# MAD76.net
KiCad netlist of a schematic drawn in EAGLE
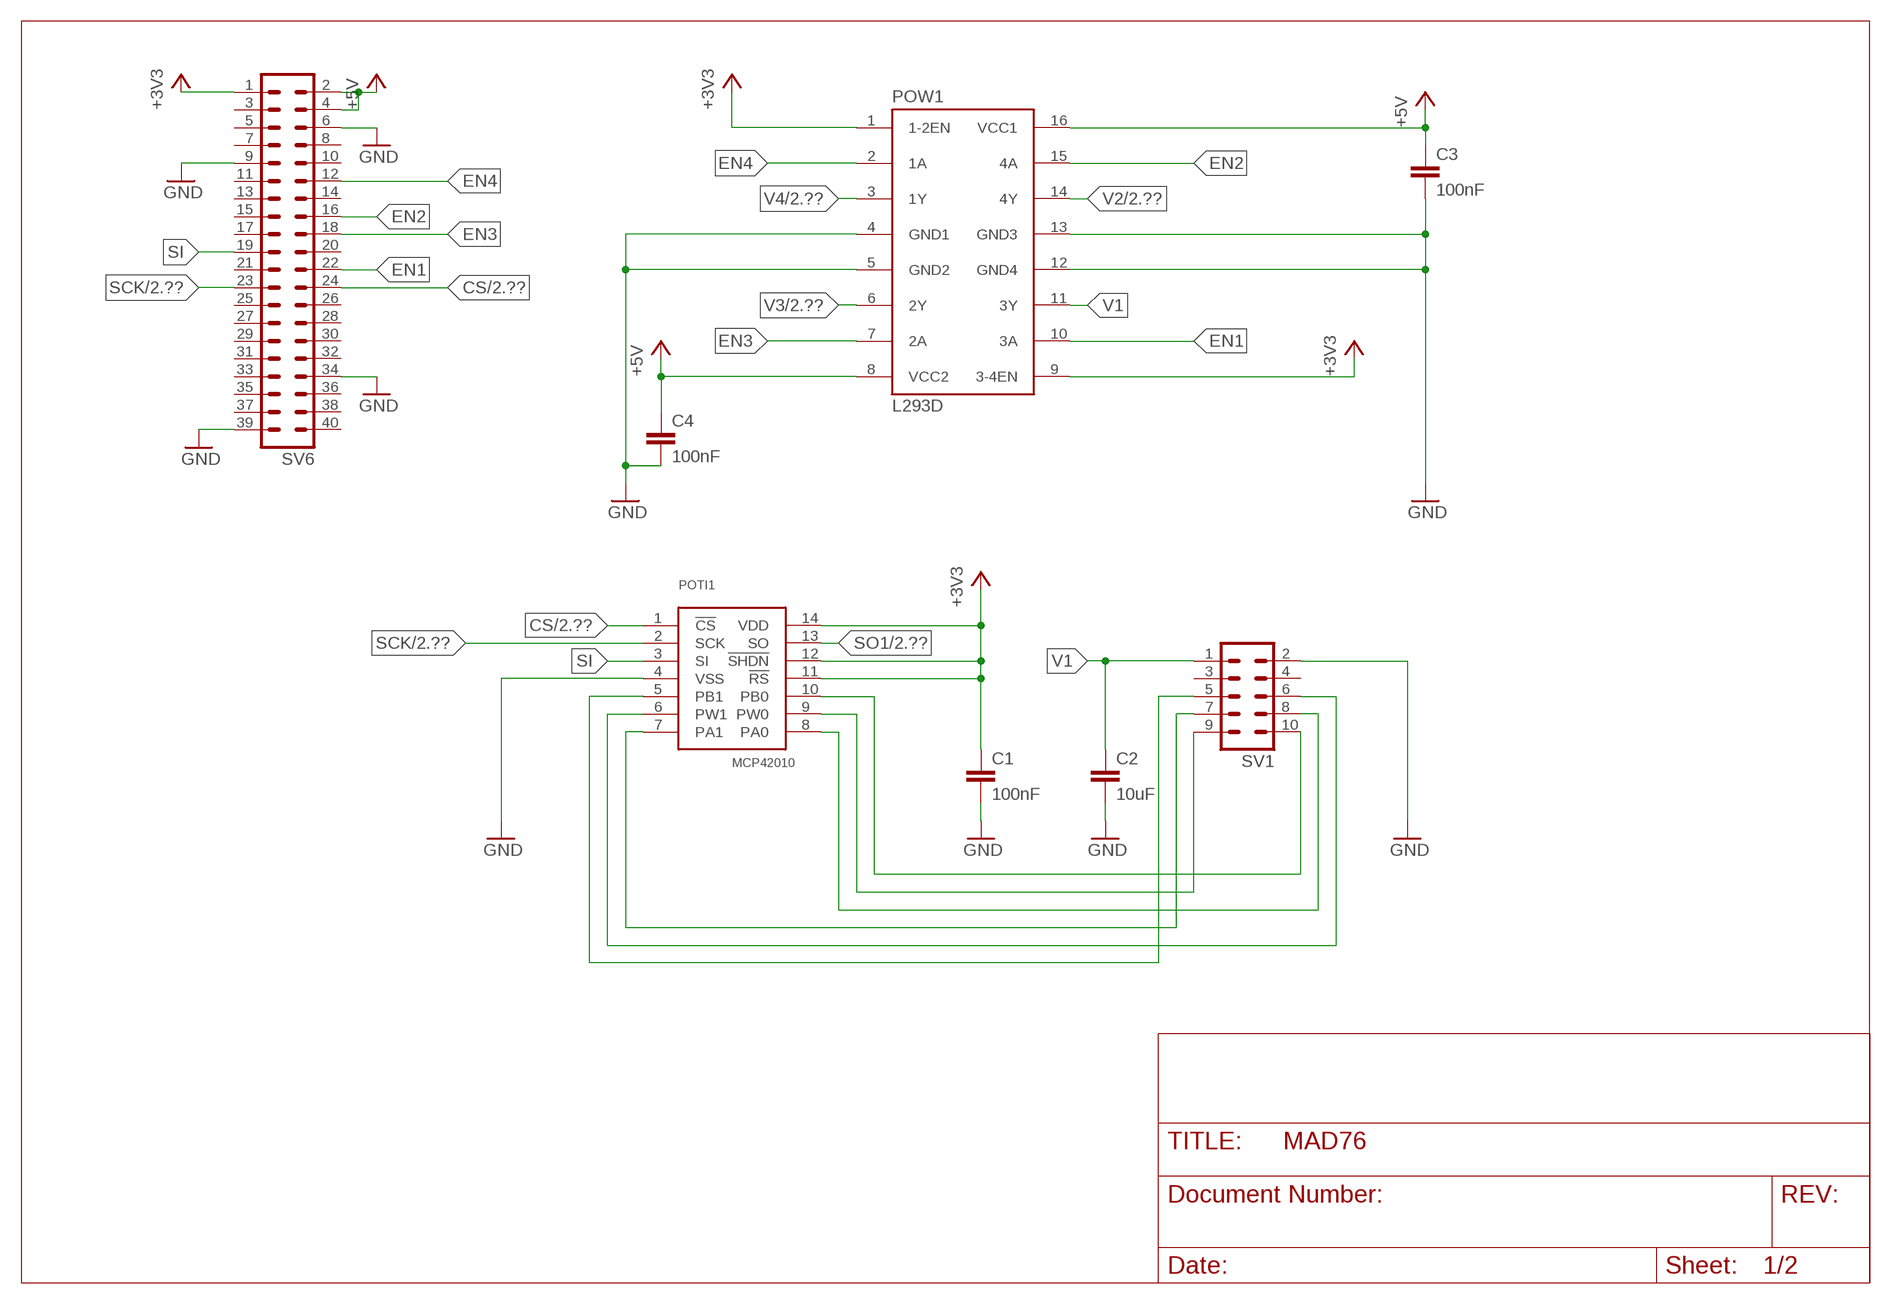
[diagram p0: schematic, sheet 1]
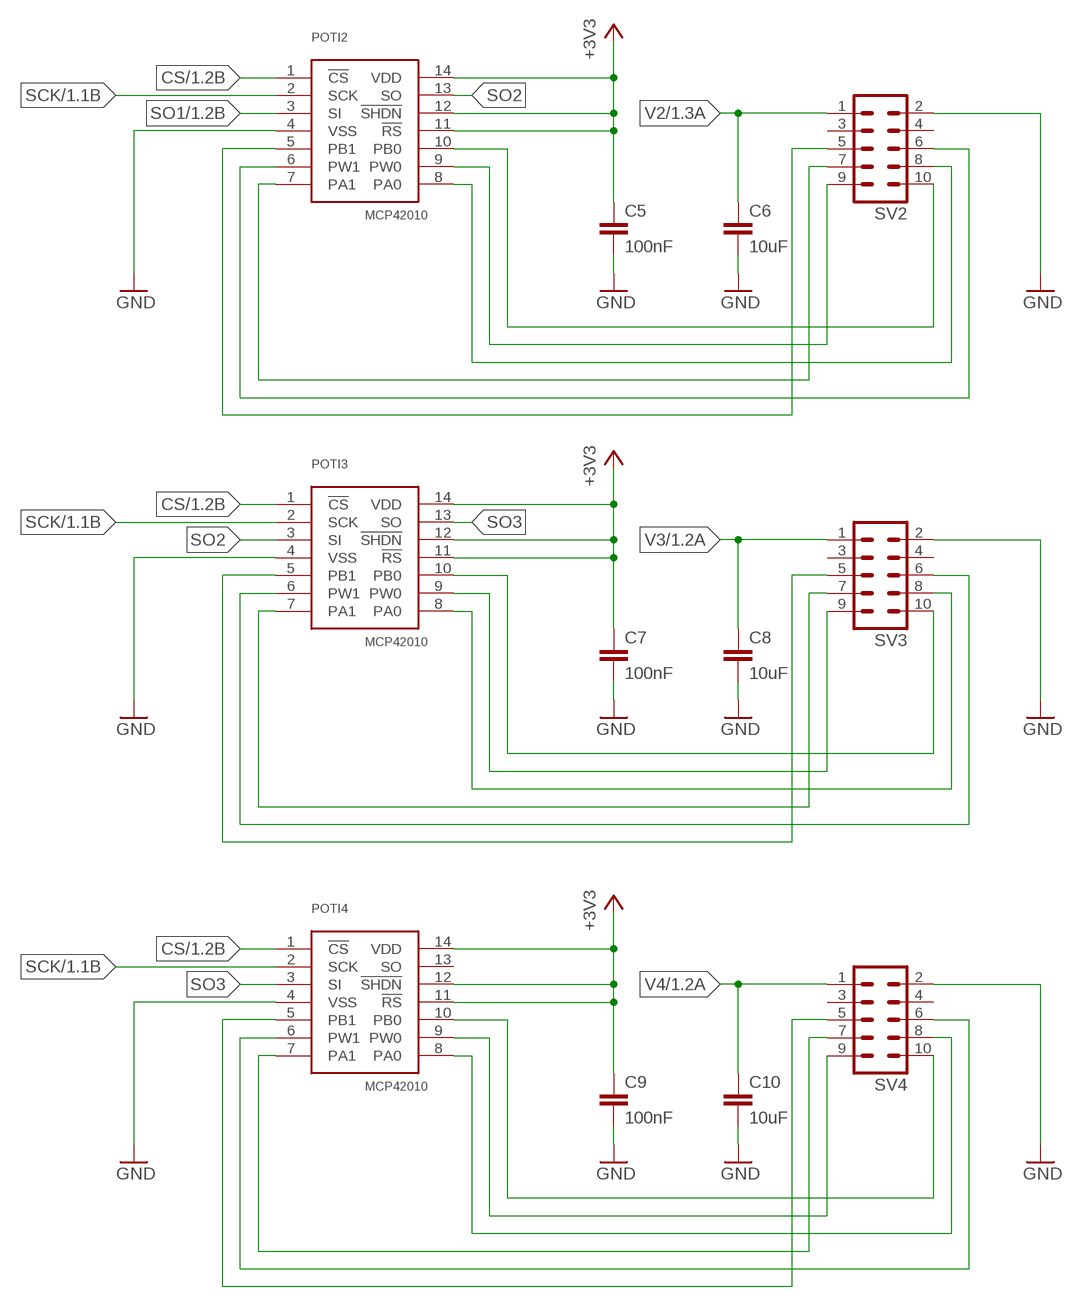
[diagram p1: schematic, sheet 2]

(export (version "E")
  (design (tool "Eeschema 10.0.6"))
  (components
    (comp (ref "C5")
      (value "100nF")
      (footprint "eagle-import:C0805")
      (libsource (lib "eagle-import") (part "C-EUC0805"))
    )
    (comp (ref "C6")
      (value "10uF")
      (footprint "eagle-import:C0805")
      (libsource (lib "eagle-import") (part "C-EUC0805"))
    )
    (comp (ref "C7")
      (value "100nF")
      (footprint "eagle-import:C0805")
      (libsource (lib "eagle-import") (part "C-EUC0805"))
    )
    (comp (ref "C8")
      (value "10uF")
      (footprint "eagle-import:C0805")
      (libsource (lib "eagle-import") (part "C-EUC0805"))
    )
    (comp (ref "C9")
      (value "100nF")
      (footprint "eagle-import:C0805")
      (libsource (lib "eagle-import") (part "C-EUC0805"))
    )
    (comp (ref "C10")
      (value "10uF")
      (footprint "eagle-import:C0805")
      (libsource (lib "eagle-import") (part "C-EUC0805"))
    )
    (comp (ref "POTI2")
      (value "MCP42010")
      (footprint "eagle-import:DIL14")
      (libsource (lib "eagle-import") (part "MCP42010"))
    )
    (comp (ref "POTI3")
      (value "MCP42010")
      (footprint "eagle-import:DIL14")
      (libsource (lib "eagle-import") (part "MCP42010"))
    )
    (comp (ref "POTI4")
      (value "MCP42010")
      (footprint "eagle-import:DIL14")
      (libsource (lib "eagle-import") (part "MCP42010"))
    )
    (comp (ref "SV2")
      (value "ML10")
      (footprint "eagle-import:ML10")
      (libsource (lib "eagle-import") (part "ML10"))
    )
    (comp (ref "SV3")
      (value "ML10")
      (footprint "eagle-import:ML10")
      (libsource (lib "eagle-import") (part "ML10"))
    )
    (comp (ref "SV4")
      (value "ML10")
      (footprint "eagle-import:ML10")
      (libsource (lib "eagle-import") (part "ML10"))
    )
    (comp (ref "C1")
      (value "100nF")
      (footprint "eagle-import:C0805")
      (libsource (lib "eagle-import") (part "C-EUC0805"))
    )
    (comp (ref "C2")
      (value "10uF")
      (footprint "eagle-import:C0805")
      (libsource (lib "eagle-import") (part "C-EUC0805"))
    )
    (comp (ref "C3")
      (value "100nF")
      (footprint "eagle-import:C0805")
      (libsource (lib "eagle-import") (part "C-EUC0805"))
    )
    (comp (ref "C4")
      (value "100nF")
      (footprint "eagle-import:C0805")
      (libsource (lib "eagle-import") (part "C-EUC0805"))
    )
    (comp (ref "POTI1")
      (value "MCP42010")
      (footprint "eagle-import:DIL14")
      (libsource (lib "eagle-import") (part "MCP42010"))
    )
    (comp (ref "POW1")
      (value "L293D")
      (footprint "eagle-import:DIL16")
      (libsource (lib "eagle-import") (part "L293D"))
    )
    (comp (ref "SV1")
      (value "ML10")
      (footprint "eagle-import:ML10")
      (libsource (lib "eagle-import") (part "ML10"))
    )
    (comp (ref "SV6")
      (value "MA20-2W_RPI")
      (footprint "eagle-import:MA20-2W_RPI")
      (libsource (lib "eagle-import") (part "MA20-2W_RPI"))
    )
  )
  (nets
    (net (code "1") (name "+3V3") (class "Default")
      (node (ref "C1") (pin "1") (pinfunction "1_1") (pintype "passive"))
      (node (ref "C5") (pin "1") (pinfunction "1_1") (pintype "passive"))
      (node (ref "C7") (pin "1") (pinfunction "1_1") (pintype "passive"))
      (node (ref "C9") (pin "1") (pinfunction "1_1") (pintype "passive"))
      (node (ref "POTI1") (pin "11") (pinfunction "~{RS}_11") (pintype "input"))
      (node (ref "POTI1") (pin "12") (pinfunction "~{SHDN}_12") (pintype "input"))
      (node (ref "POTI1") (pin "14") (pinfunction "VDD_14") (pintype "power_in"))
      (node (ref "POTI2") (pin "11") (pinfunction "~{RS}_11") (pintype "input"))
      (node (ref "POTI2") (pin "12") (pinfunction "~{SHDN}_12") (pintype "input"))
      (node (ref "POTI2") (pin "14") (pinfunction "VDD_14") (pintype "power_in"))
      (node (ref "POTI3") (pin "11") (pinfunction "~{RS}_11") (pintype "input"))
      (node (ref "POTI3") (pin "12") (pinfunction "~{SHDN}_12") (pintype "input"))
      (node (ref "POTI3") (pin "14") (pinfunction "VDD_14") (pintype "power_in"))
      (node (ref "POTI4") (pin "11") (pinfunction "~{RS}_11") (pintype "input"))
      (node (ref "POTI4") (pin "12") (pinfunction "~{SHDN}_12") (pintype "input"))
      (node (ref "POTI4") (pin "14") (pinfunction "VDD_14") (pintype "power_in"))
      (node (ref "POW1") (pin "1") (pinfunction "1-2EN_1") (pintype "input"))
      (node (ref "POW1") (pin "9") (pinfunction "3-4EN_9") (pintype "input"))
      (node (ref "SV6") (pin "1") (pinfunction "1_1") (pintype "passive"))
    )
    (net (code "2") (name "+5V") (class "Default")
      (node (ref "C3") (pin "1") (pinfunction "1_1") (pintype "passive"))
      (node (ref "C4") (pin "1") (pinfunction "1_1") (pintype "passive"))
      (node (ref "POW1") (pin "16") (pinfunction "VCC1_16") (pintype "power_in"))
      (node (ref "POW1") (pin "8") (pinfunction "VCC2_8") (pintype "power_in"))
      (node (ref "SV6") (pin "2") (pinfunction "2_2") (pintype "passive"))
      (node (ref "SV6") (pin "4") (pinfunction "4_4") (pintype "passive"))
    )
    (net (code "3") (name "CS") (class "Default")
      (node (ref "POTI1") (pin "1") (pinfunction "~{CS}_1") (pintype "input"))
      (node (ref "POTI2") (pin "1") (pinfunction "~{CS}_1") (pintype "input"))
      (node (ref "POTI3") (pin "1") (pinfunction "~{CS}_1") (pintype "input"))
      (node (ref "POTI4") (pin "1") (pinfunction "~{CS}_1") (pintype "input"))
      (node (ref "SV6") (pin "24") (pinfunction "24_24") (pintype "passive"))
    )
    (net (code "4") (name "EN1") (class "Default")
      (node (ref "POW1") (pin "10") (pinfunction "3A_10") (pintype "input"))
      (node (ref "SV6") (pin "22") (pinfunction "22_22") (pintype "passive"))
    )
    (net (code "5") (name "EN2") (class "Default")
      (node (ref "POW1") (pin "15") (pinfunction "4A_15") (pintype "input"))
      (node (ref "SV6") (pin "16") (pinfunction "16_16") (pintype "passive"))
    )
    (net (code "6") (name "EN3") (class "Default")
      (node (ref "POW1") (pin "7") (pinfunction "2A_7") (pintype "input"))
      (node (ref "SV6") (pin "18") (pinfunction "18_18") (pintype "passive"))
    )
    (net (code "7") (name "EN4") (class "Default")
      (node (ref "POW1") (pin "2") (pinfunction "1A_2") (pintype "input"))
      (node (ref "SV6") (pin "12") (pinfunction "12_12") (pintype "passive"))
    )
    (net (code "8") (name "GND") (class "Default")
      (node (ref "C1") (pin "2") (pinfunction "2_2") (pintype "passive"))
      (node (ref "C10") (pin "2") (pinfunction "2_2") (pintype "passive"))
      (node (ref "C2") (pin "2") (pinfunction "2_2") (pintype "passive"))
      (node (ref "C3") (pin "2") (pinfunction "2_2") (pintype "passive"))
      (node (ref "C4") (pin "2") (pinfunction "2_2") (pintype "passive"))
      (node (ref "C5") (pin "2") (pinfunction "2_2") (pintype "passive"))
      (node (ref "C6") (pin "2") (pinfunction "2_2") (pintype "passive"))
      (node (ref "C7") (pin "2") (pinfunction "2_2") (pintype "passive"))
      (node (ref "C8") (pin "2") (pinfunction "2_2") (pintype "passive"))
      (node (ref "C9") (pin "2") (pinfunction "2_2") (pintype "passive"))
      (node (ref "POTI1") (pin "4") (pinfunction "VSS_4") (pintype "power_in"))
      (node (ref "POTI2") (pin "4") (pinfunction "VSS_4") (pintype "power_in"))
      (node (ref "POTI3") (pin "4") (pinfunction "VSS_4") (pintype "power_in"))
      (node (ref "POTI4") (pin "4") (pinfunction "VSS_4") (pintype "power_in"))
      (node (ref "POW1") (pin "12") (pinfunction "GND4_12") (pintype "power_in"))
      (node (ref "POW1") (pin "13") (pinfunction "GND3_13") (pintype "power_in"))
      (node (ref "POW1") (pin "4") (pinfunction "GND1_4") (pintype "power_in"))
      (node (ref "POW1") (pin "5") (pinfunction "GND2_5") (pintype "power_in"))
      (node (ref "SV1") (pin "2") (pinfunction "2_2") (pintype "passive"))
      (node (ref "SV2") (pin "2") (pinfunction "2_2") (pintype "passive"))
      (node (ref "SV3") (pin "2") (pinfunction "2_2") (pintype "passive"))
      (node (ref "SV4") (pin "2") (pinfunction "2_2") (pintype "passive"))
      (node (ref "SV6") (pin "34") (pinfunction "34_34") (pintype "passive"))
      (node (ref "SV6") (pin "39") (pinfunction "39_39") (pintype "passive"))
      (node (ref "SV6") (pin "6") (pinfunction "6_6") (pintype "passive"))
      (node (ref "SV6") (pin "9") (pinfunction "9_9") (pintype "passive"))
    )
    (net (code "9") (name "Net-(POTI1-PA0)") (class "Default")
      (node (ref "POTI1") (pin "8") (pinfunction "PA0_8") (pintype "passive"))
      (node (ref "SV1") (pin "8") (pinfunction "8_8") (pintype "passive"))
    )
    (net (code "10") (name "Net-(POTI1-PA1)") (class "Default")
      (node (ref "POTI1") (pin "7") (pinfunction "PA1_7") (pintype "passive"))
      (node (ref "SV1") (pin "7") (pinfunction "7_7") (pintype "passive"))
    )
    (net (code "11") (name "Net-(POTI1-PB0)") (class "Default")
      (node (ref "POTI1") (pin "10") (pinfunction "PB0_10") (pintype "passive"))
      (node (ref "SV1") (pin "10") (pinfunction "10_10") (pintype "passive"))
    )
    (net (code "12") (name "Net-(POTI1-PB1)") (class "Default")
      (node (ref "POTI1") (pin "5") (pinfunction "PB1_5") (pintype "passive"))
      (node (ref "SV1") (pin "5") (pinfunction "5_5") (pintype "passive"))
    )
    (net (code "13") (name "Net-(POTI1-PW0)") (class "Default")
      (node (ref "POTI1") (pin "9") (pinfunction "PW0_9") (pintype "passive"))
      (node (ref "SV1") (pin "9") (pinfunction "9_9") (pintype "passive"))
    )
    (net (code "14") (name "Net-(POTI1-PW1)") (class "Default")
      (node (ref "POTI1") (pin "6") (pinfunction "PW1_6") (pintype "passive"))
      (node (ref "SV1") (pin "6") (pinfunction "6_6") (pintype "passive"))
    )
    (net (code "15") (name "Net-(POTI2-PA0)") (class "Default")
      (node (ref "POTI2") (pin "8") (pinfunction "PA0_8") (pintype "passive"))
      (node (ref "SV2") (pin "8") (pinfunction "8_8") (pintype "passive"))
    )
    (net (code "16") (name "Net-(POTI2-PA1)") (class "Default")
      (node (ref "POTI2") (pin "7") (pinfunction "PA1_7") (pintype "passive"))
      (node (ref "SV2") (pin "7") (pinfunction "7_7") (pintype "passive"))
    )
    (net (code "17") (name "Net-(POTI2-PB0)") (class "Default")
      (node (ref "POTI2") (pin "10") (pinfunction "PB0_10") (pintype "passive"))
      (node (ref "SV2") (pin "10") (pinfunction "10_10") (pintype "passive"))
    )
    (net (code "18") (name "Net-(POTI2-PB1)") (class "Default")
      (node (ref "POTI2") (pin "5") (pinfunction "PB1_5") (pintype "passive"))
      (node (ref "SV2") (pin "5") (pinfunction "5_5") (pintype "passive"))
    )
    (net (code "19") (name "Net-(POTI2-PW0)") (class "Default")
      (node (ref "POTI2") (pin "9") (pinfunction "PW0_9") (pintype "passive"))
      (node (ref "SV2") (pin "9") (pinfunction "9_9") (pintype "passive"))
    )
    (net (code "20") (name "Net-(POTI2-PW1)") (class "Default")
      (node (ref "POTI2") (pin "6") (pinfunction "PW1_6") (pintype "passive"))
      (node (ref "SV2") (pin "6") (pinfunction "6_6") (pintype "passive"))
    )
    (net (code "21") (name "Net-(POTI3-PA0)") (class "Default")
      (node (ref "POTI3") (pin "8") (pinfunction "PA0_8") (pintype "passive"))
      (node (ref "SV3") (pin "8") (pinfunction "8_8") (pintype "passive"))
    )
    (net (code "22") (name "Net-(POTI3-PA1)") (class "Default")
      (node (ref "POTI3") (pin "7") (pinfunction "PA1_7") (pintype "passive"))
      (node (ref "SV3") (pin "7") (pinfunction "7_7") (pintype "passive"))
    )
    (net (code "23") (name "Net-(POTI3-PB0)") (class "Default")
      (node (ref "POTI3") (pin "10") (pinfunction "PB0_10") (pintype "passive"))
      (node (ref "SV3") (pin "10") (pinfunction "10_10") (pintype "passive"))
    )
    (net (code "24") (name "Net-(POTI3-PB1)") (class "Default")
      (node (ref "POTI3") (pin "5") (pinfunction "PB1_5") (pintype "passive"))
      (node (ref "SV3") (pin "5") (pinfunction "5_5") (pintype "passive"))
    )
    (net (code "25") (name "Net-(POTI3-PW0)") (class "Default")
      (node (ref "POTI3") (pin "9") (pinfunction "PW0_9") (pintype "passive"))
      (node (ref "SV3") (pin "9") (pinfunction "9_9") (pintype "passive"))
    )
    (net (code "26") (name "Net-(POTI3-PW1)") (class "Default")
      (node (ref "POTI3") (pin "6") (pinfunction "PW1_6") (pintype "passive"))
      (node (ref "SV3") (pin "6") (pinfunction "6_6") (pintype "passive"))
    )
    (net (code "27") (name "Net-(POTI4-PA0)") (class "Default")
      (node (ref "POTI4") (pin "8") (pinfunction "PA0_8") (pintype "passive"))
      (node (ref "SV4") (pin "8") (pinfunction "8_8") (pintype "passive"))
    )
    (net (code "28") (name "Net-(POTI4-PA1)") (class "Default")
      (node (ref "POTI4") (pin "7") (pinfunction "PA1_7") (pintype "passive"))
      (node (ref "SV4") (pin "7") (pinfunction "7_7") (pintype "passive"))
    )
    (net (code "29") (name "Net-(POTI4-PB0)") (class "Default")
      (node (ref "POTI4") (pin "10") (pinfunction "PB0_10") (pintype "passive"))
      (node (ref "SV4") (pin "10") (pinfunction "10_10") (pintype "passive"))
    )
    (net (code "30") (name "Net-(POTI4-PB1)") (class "Default")
      (node (ref "POTI4") (pin "5") (pinfunction "PB1_5") (pintype "passive"))
      (node (ref "SV4") (pin "5") (pinfunction "5_5") (pintype "passive"))
    )
    (net (code "31") (name "Net-(POTI4-PW0)") (class "Default")
      (node (ref "POTI4") (pin "9") (pinfunction "PW0_9") (pintype "passive"))
      (node (ref "SV4") (pin "9") (pinfunction "9_9") (pintype "passive"))
    )
    (net (code "32") (name "Net-(POTI4-PW1)") (class "Default")
      (node (ref "POTI4") (pin "6") (pinfunction "PW1_6") (pintype "passive"))
      (node (ref "SV4") (pin "6") (pinfunction "6_6") (pintype "passive"))
    )
    (net (code "33") (name "SCK") (class "Default")
      (node (ref "POTI1") (pin "2") (pinfunction "SCK_2") (pintype "input"))
      (node (ref "POTI2") (pin "2") (pinfunction "SCK_2") (pintype "input"))
      (node (ref "POTI3") (pin "2") (pinfunction "SCK_2") (pintype "input"))
      (node (ref "POTI4") (pin "2") (pinfunction "SCK_2") (pintype "input"))
      (node (ref "SV6") (pin "23") (pinfunction "23_23") (pintype "passive"))
    )
    (net (code "34") (name "SI") (class "Default")
      (node (ref "POTI1") (pin "3") (pinfunction "SI_3") (pintype "input"))
      (node (ref "SV6") (pin "19") (pinfunction "19_19") (pintype "passive"))
    )
    (net (code "35") (name "SO1") (class "Default")
      (node (ref "POTI1") (pin "13") (pinfunction "SO_13") (pintype "output"))
      (node (ref "POTI2") (pin "3") (pinfunction "SI_3") (pintype "input"))
    )
    (net (code "36") (name "SO2") (class "Default")
      (node (ref "POTI2") (pin "13") (pinfunction "SO_13") (pintype "output"))
      (node (ref "POTI3") (pin "3") (pinfunction "SI_3") (pintype "input"))
    )
    (net (code "37") (name "SO3") (class "Default")
      (node (ref "POTI3") (pin "13") (pinfunction "SO_13") (pintype "output"))
      (node (ref "POTI4") (pin "3") (pinfunction "SI_3") (pintype "input"))
    )
    (net (code "38") (name "V1") (class "Default")
      (node (ref "C2") (pin "1") (pinfunction "1_1") (pintype "passive"))
      (node (ref "POW1") (pin "11") (pinfunction "3Y_11") (pintype "output"))
      (node (ref "SV1") (pin "1") (pinfunction "1_1") (pintype "passive"))
    )
    (net (code "39") (name "V2") (class "Default")
      (node (ref "C6") (pin "1") (pinfunction "1_1") (pintype "passive"))
      (node (ref "POW1") (pin "14") (pinfunction "4Y_14") (pintype "output"))
      (node (ref "SV2") (pin "1") (pinfunction "1_1") (pintype "passive"))
    )
    (net (code "40") (name "V3") (class "Default")
      (node (ref "C8") (pin "1") (pinfunction "1_1") (pintype "passive"))
      (node (ref "POW1") (pin "6") (pinfunction "2Y_6") (pintype "output"))
      (node (ref "SV3") (pin "1") (pinfunction "1_1") (pintype "passive"))
    )
    (net (code "41") (name "V4") (class "Default")
      (node (ref "C10") (pin "1") (pinfunction "1_1") (pintype "passive"))
      (node (ref "POW1") (pin "3") (pinfunction "1Y_3") (pintype "output"))
      (node (ref "SV4") (pin "1") (pinfunction "1_1") (pintype "passive"))
    )
    (net (code "42") (name "unconnected-(POTI4-SO-Pad13)") (class "Default")
      (node (ref "POTI4") (pin "13") (pinfunction "SO_13") (pintype "output"))
    )
    (net (code "43") (name "unconnected-(SV1-Pad3)") (class "Default")
      (node (ref "SV1") (pin "3") (pinfunction "3_3") (pintype "passive"))
    )
    (net (code "44") (name "unconnected-(SV1-Pad4)") (class "Default")
      (node (ref "SV1") (pin "4") (pinfunction "4_4") (pintype "passive"))
    )
    (net (code "45") (name "unconnected-(SV2-Pad3)") (class "Default")
      (node (ref "SV2") (pin "3") (pinfunction "3_3") (pintype "passive"))
    )
    (net (code "46") (name "unconnected-(SV2-Pad4)") (class "Default")
      (node (ref "SV2") (pin "4") (pinfunction "4_4") (pintype "passive"))
    )
    (net (code "47") (name "unconnected-(SV3-Pad3)") (class "Default")
      (node (ref "SV3") (pin "3") (pinfunction "3_3") (pintype "passive"))
    )
    (net (code "48") (name "unconnected-(SV3-Pad4)") (class "Default")
      (node (ref "SV3") (pin "4") (pinfunction "4_4") (pintype "passive"))
    )
    (net (code "49") (name "unconnected-(SV4-Pad3)") (class "Default")
      (node (ref "SV4") (pin "3") (pinfunction "3_3") (pintype "passive"))
    )
    (net (code "50") (name "unconnected-(SV4-Pad4)") (class "Default")
      (node (ref "SV4") (pin "4") (pinfunction "4_4") (pintype "passive"))
    )
    (net (code "51") (name "unconnected-(SV6-Pad3)") (class "Default")
      (node (ref "SV6") (pin "3") (pinfunction "3_3") (pintype "passive"))
    )
    (net (code "52") (name "unconnected-(SV6-Pad5)") (class "Default")
      (node (ref "SV6") (pin "5") (pinfunction "5_5") (pintype "passive"))
    )
    (net (code "53") (name "unconnected-(SV6-Pad7)") (class "Default")
      (node (ref "SV6") (pin "7") (pinfunction "7_7") (pintype "passive"))
    )
    (net (code "54") (name "unconnected-(SV6-Pad8)") (class "Default")
      (node (ref "SV6") (pin "8") (pinfunction "8_8") (pintype "passive"))
    )
    (net (code "55") (name "unconnected-(SV6-Pad10)") (class "Default")
      (node (ref "SV6") (pin "10") (pinfunction "10_10") (pintype "passive"))
    )
    (net (code "56") (name "unconnected-(SV6-Pad11)") (class "Default")
      (node (ref "SV6") (pin "11") (pinfunction "11_11") (pintype "passive"))
    )
    (net (code "57") (name "unconnected-(SV6-Pad13)") (class "Default")
      (node (ref "SV6") (pin "13") (pinfunction "13_13") (pintype "passive"))
    )
    (net (code "58") (name "unconnected-(SV6-Pad14)") (class "Default")
      (node (ref "SV6") (pin "14") (pinfunction "14_14") (pintype "passive"))
    )
    (net (code "59") (name "unconnected-(SV6-Pad15)") (class "Default")
      (node (ref "SV6") (pin "15") (pinfunction "15_15") (pintype "passive"))
    )
    (net (code "60") (name "unconnected-(SV6-Pad17)") (class "Default")
      (node (ref "SV6") (pin "17") (pinfunction "17_17") (pintype "passive"))
    )
    (net (code "61") (name "unconnected-(SV6-Pad20)") (class "Default")
      (node (ref "SV6") (pin "20") (pinfunction "20_20") (pintype "passive"))
    )
    (net (code "62") (name "unconnected-(SV6-Pad21)") (class "Default")
      (node (ref "SV6") (pin "21") (pinfunction "21_21") (pintype "passive"))
    )
    (net (code "63") (name "unconnected-(SV6-Pad25)") (class "Default")
      (node (ref "SV6") (pin "25") (pinfunction "25_25") (pintype "passive"))
    )
    (net (code "64") (name "unconnected-(SV6-Pad26)") (class "Default")
      (node (ref "SV6") (pin "26") (pinfunction "26_26") (pintype "passive"))
    )
    (net (code "65") (name "unconnected-(SV6-Pad27)") (class "Default")
      (node (ref "SV6") (pin "27") (pinfunction "27_27") (pintype "passive"))
    )
    (net (code "66") (name "unconnected-(SV6-Pad28)") (class "Default")
      (node (ref "SV6") (pin "28") (pinfunction "28_28") (pintype "passive"))
    )
    (net (code "67") (name "unconnected-(SV6-Pad29)") (class "Default")
      (node (ref "SV6") (pin "29") (pinfunction "29_29") (pintype "passive"))
    )
    (net (code "68") (name "unconnected-(SV6-Pad30)") (class "Default")
      (node (ref "SV6") (pin "30") (pinfunction "30_30") (pintype "passive"))
    )
    (net (code "69") (name "unconnected-(SV6-Pad31)") (class "Default")
      (node (ref "SV6") (pin "31") (pinfunction "31_31") (pintype "passive"))
    )
    (net (code "70") (name "unconnected-(SV6-Pad32)") (class "Default")
      (node (ref "SV6") (pin "32") (pinfunction "32_32") (pintype "passive"))
    )
    (net (code "71") (name "unconnected-(SV6-Pad33)") (class "Default")
      (node (ref "SV6") (pin "33") (pinfunction "33_33") (pintype "passive"))
    )
    (net (code "72") (name "unconnected-(SV6-Pad35)") (class "Default")
      (node (ref "SV6") (pin "35") (pinfunction "35_35") (pintype "passive"))
    )
    (net (code "73") (name "unconnected-(SV6-Pad36)") (class "Default")
      (node (ref "SV6") (pin "36") (pinfunction "36_36") (pintype "passive"))
    )
    (net (code "74") (name "unconnected-(SV6-Pad37)") (class "Default")
      (node (ref "SV6") (pin "37") (pinfunction "37_37") (pintype "passive"))
    )
    (net (code "75") (name "unconnected-(SV6-Pad38)") (class "Default")
      (node (ref "SV6") (pin "38") (pinfunction "38_38") (pintype "passive"))
    )
    (net (code "76") (name "unconnected-(SV6-Pad40)") (class "Default")
      (node (ref "SV6") (pin "40") (pinfunction "40_40") (pintype "passive"))
    )
  )
)
